# 16to4_Decoder.net
KiCad netlist of a schematic drawn in EAGLE
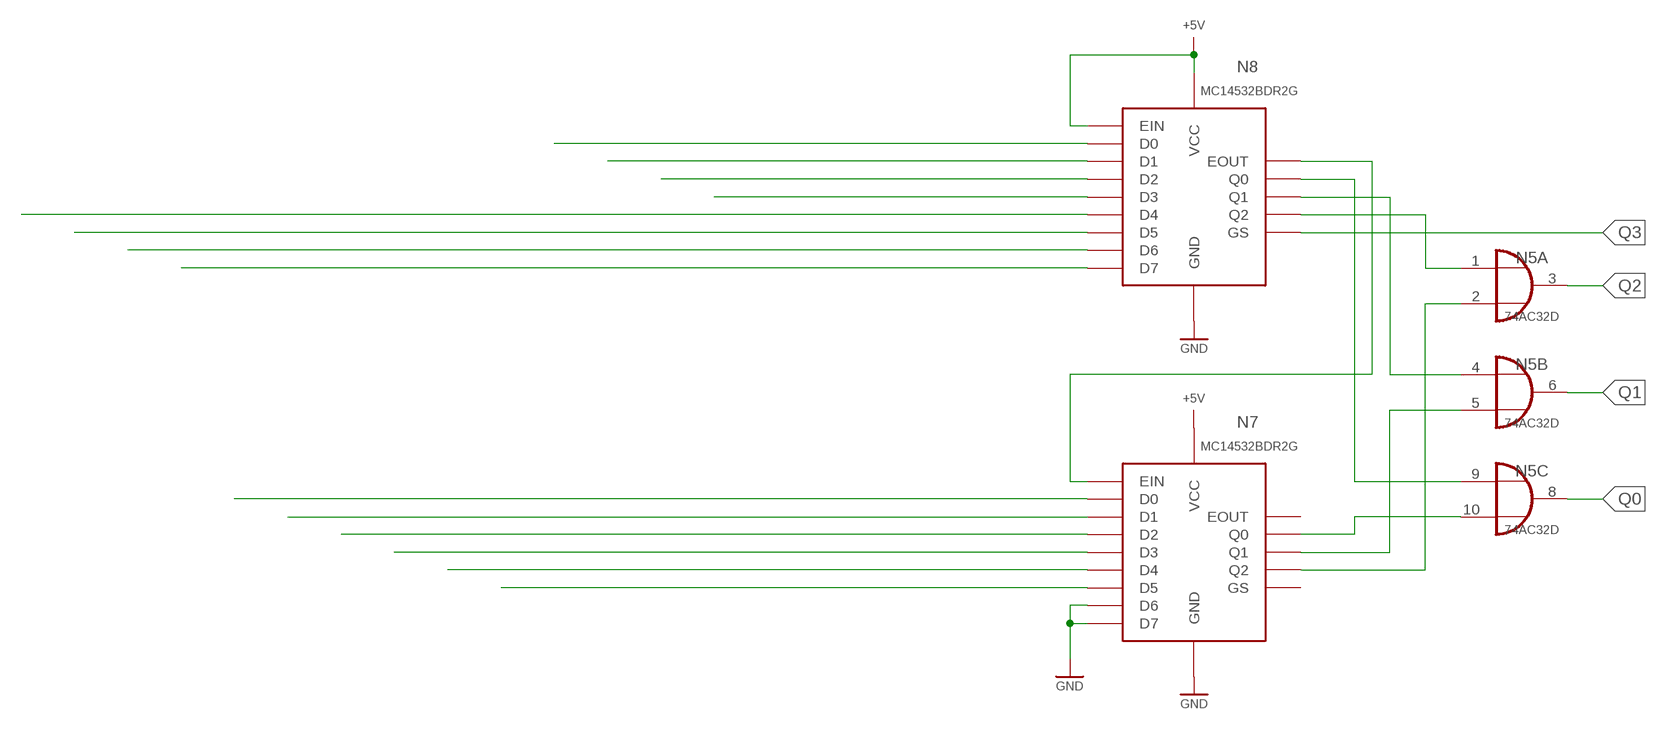
[diagram p0: schematic, sheet 1]

(export (version "E")
  (design (tool "Eeschema 10.0.6"))
  (components
    (comp (ref "N5")
      (value "74AC32D")
      (footprint "eagle-import:SO14")
      (libsource (lib "eagle-import") (part "7432DAC"))
    )
    (comp (ref "N7")
      (value "MC14532BDR2G")
      (footprint "eagle-import:SOIC16")
      (libsource (lib "eagle-import") (part "MC14532BDR2G"))
    )
    (comp (ref "N8")
      (value "MC14532BDR2G")
      (footprint "eagle-import:SOIC16")
      (libsource (lib "eagle-import") (part "MC14532BDR2G"))
    )
  )
  (nets
    (net (code "1") (name "+5V") (class "Default")
      (node (ref "N7") (pin "16") (pinfunction "VCC_16") (pintype "bidirectional"))
      (node (ref "N8") (pin "16") (pinfunction "VCC_16") (pintype "bidirectional"))
      (node (ref "N8") (pin "5") (pinfunction "EIN_5") (pintype "bidirectional"))
    )
    (net (code "2") (name "GND") (class "Default")
      (node (ref "N7") (pin "3") (pinfunction "D6_3") (pintype "bidirectional"))
      (node (ref "N7") (pin "4") (pinfunction "D7_4") (pintype "bidirectional"))
      (node (ref "N7") (pin "8") (pinfunction "GND_8") (pintype "bidirectional"))
      (node (ref "N8") (pin "8") (pinfunction "GND_8") (pintype "bidirectional"))
    )
    (net (code "3") (name "Net-(N5A-I0)") (class "Default")
      (node (ref "N5") (pin "1") (pinfunction "I0_1") (pintype "input"))
      (node (ref "N8") (pin "6") (pinfunction "Q2_6") (pintype "bidirectional"))
    )
    (net (code "4") (name "Net-(N5A-I1)") (class "Default")
      (node (ref "N5") (pin "2") (pinfunction "I1_2") (pintype "input"))
      (node (ref "N7") (pin "6") (pinfunction "Q2_6") (pintype "bidirectional"))
    )
    (net (code "5") (name "Net-(N5B-I0)") (class "Default")
      (node (ref "N5") (pin "4") (pinfunction "I0_4") (pintype "input"))
      (node (ref "N8") (pin "7") (pinfunction "Q1_7") (pintype "bidirectional"))
    )
    (net (code "6") (name "Net-(N5B-I1)") (class "Default")
      (node (ref "N5") (pin "5") (pinfunction "I1_5") (pintype "input"))
      (node (ref "N7") (pin "7") (pinfunction "Q1_7") (pintype "bidirectional"))
    )
    (net (code "7") (name "Net-(N5C-I0)") (class "Default")
      (node (ref "N5") (pin "9") (pinfunction "I0_9") (pintype "input"))
      (node (ref "N8") (pin "9") (pinfunction "Q0_9") (pintype "bidirectional"))
    )
    (net (code "8") (name "Net-(N5C-I1)") (class "Default")
      (node (ref "N5") (pin "10") (pinfunction "I1_10") (pintype "input"))
      (node (ref "N7") (pin "9") (pinfunction "Q0_9") (pintype "bidirectional"))
    )
    (net (code "9") (name "Net-(N7-EIN)") (class "Default")
      (node (ref "N7") (pin "5") (pinfunction "EIN_5") (pintype "bidirectional"))
      (node (ref "N8") (pin "15") (pinfunction "EOUT_15") (pintype "bidirectional"))
    )
    (net (code "10") (name "Q0") (class "Default")
      (node (ref "N5") (pin "8") (pinfunction "O_8") (pintype "output"))
    )
    (net (code "11") (name "Q1") (class "Default")
      (node (ref "N5") (pin "6") (pinfunction "O_6") (pintype "output"))
    )
    (net (code "12") (name "Q2") (class "Default")
      (node (ref "N5") (pin "3") (pinfunction "O_3") (pintype "output"))
    )
    (net (code "13") (name "Q3") (class "Default")
      (node (ref "N8") (pin "14") (pinfunction "GS_14") (pintype "bidirectional"))
    )
    (net (code "14") (name "unconnected-(N7-D0-Pad10)") (class "Default")
      (node (ref "N7") (pin "10") (pinfunction "D0_10") (pintype "bidirectional"))
    )
    (net (code "15") (name "unconnected-(N7-D1-Pad11)") (class "Default")
      (node (ref "N7") (pin "11") (pinfunction "D1_11") (pintype "bidirectional"))
    )
    (net (code "16") (name "unconnected-(N7-D2-Pad12)") (class "Default")
      (node (ref "N7") (pin "12") (pinfunction "D2_12") (pintype "bidirectional"))
    )
    (net (code "17") (name "unconnected-(N7-D3-Pad13)") (class "Default")
      (node (ref "N7") (pin "13") (pinfunction "D3_13") (pintype "bidirectional"))
    )
    (net (code "18") (name "unconnected-(N7-D4-Pad1)") (class "Default")
      (node (ref "N7") (pin "1") (pinfunction "D4_1") (pintype "bidirectional"))
    )
    (net (code "19") (name "unconnected-(N7-D5-Pad2)") (class "Default")
      (node (ref "N7") (pin "2") (pinfunction "D5_2") (pintype "bidirectional"))
    )
    (net (code "20") (name "unconnected-(N7-EOUT-Pad15)") (class "Default")
      (node (ref "N7") (pin "15") (pinfunction "EOUT_15") (pintype "bidirectional"))
    )
    (net (code "21") (name "unconnected-(N7-GS-Pad14)") (class "Default")
      (node (ref "N7") (pin "14") (pinfunction "GS_14") (pintype "bidirectional"))
    )
    (net (code "22") (name "unconnected-(N8-D0-Pad10)") (class "Default")
      (node (ref "N8") (pin "10") (pinfunction "D0_10") (pintype "bidirectional"))
    )
    (net (code "23") (name "unconnected-(N8-D1-Pad11)") (class "Default")
      (node (ref "N8") (pin "11") (pinfunction "D1_11") (pintype "bidirectional"))
    )
    (net (code "24") (name "unconnected-(N8-D2-Pad12)") (class "Default")
      (node (ref "N8") (pin "12") (pinfunction "D2_12") (pintype "bidirectional"))
    )
    (net (code "25") (name "unconnected-(N8-D3-Pad13)") (class "Default")
      (node (ref "N8") (pin "13") (pinfunction "D3_13") (pintype "bidirectional"))
    )
    (net (code "26") (name "unconnected-(N8-D4-Pad1)") (class "Default")
      (node (ref "N8") (pin "1") (pinfunction "D4_1") (pintype "bidirectional"))
    )
    (net (code "27") (name "unconnected-(N8-D5-Pad2)") (class "Default")
      (node (ref "N8") (pin "2") (pinfunction "D5_2") (pintype "bidirectional"))
    )
    (net (code "28") (name "unconnected-(N8-D6-Pad3)") (class "Default")
      (node (ref "N8") (pin "3") (pinfunction "D6_3") (pintype "bidirectional"))
    )
    (net (code "29") (name "unconnected-(N8-D7-Pad4)") (class "Default")
      (node (ref "N8") (pin "4") (pinfunction "D7_4") (pintype "bidirectional"))
    )
  )
)
